# mini_ups.net
KiCad netlist of a schematic drawn in Altium Designer
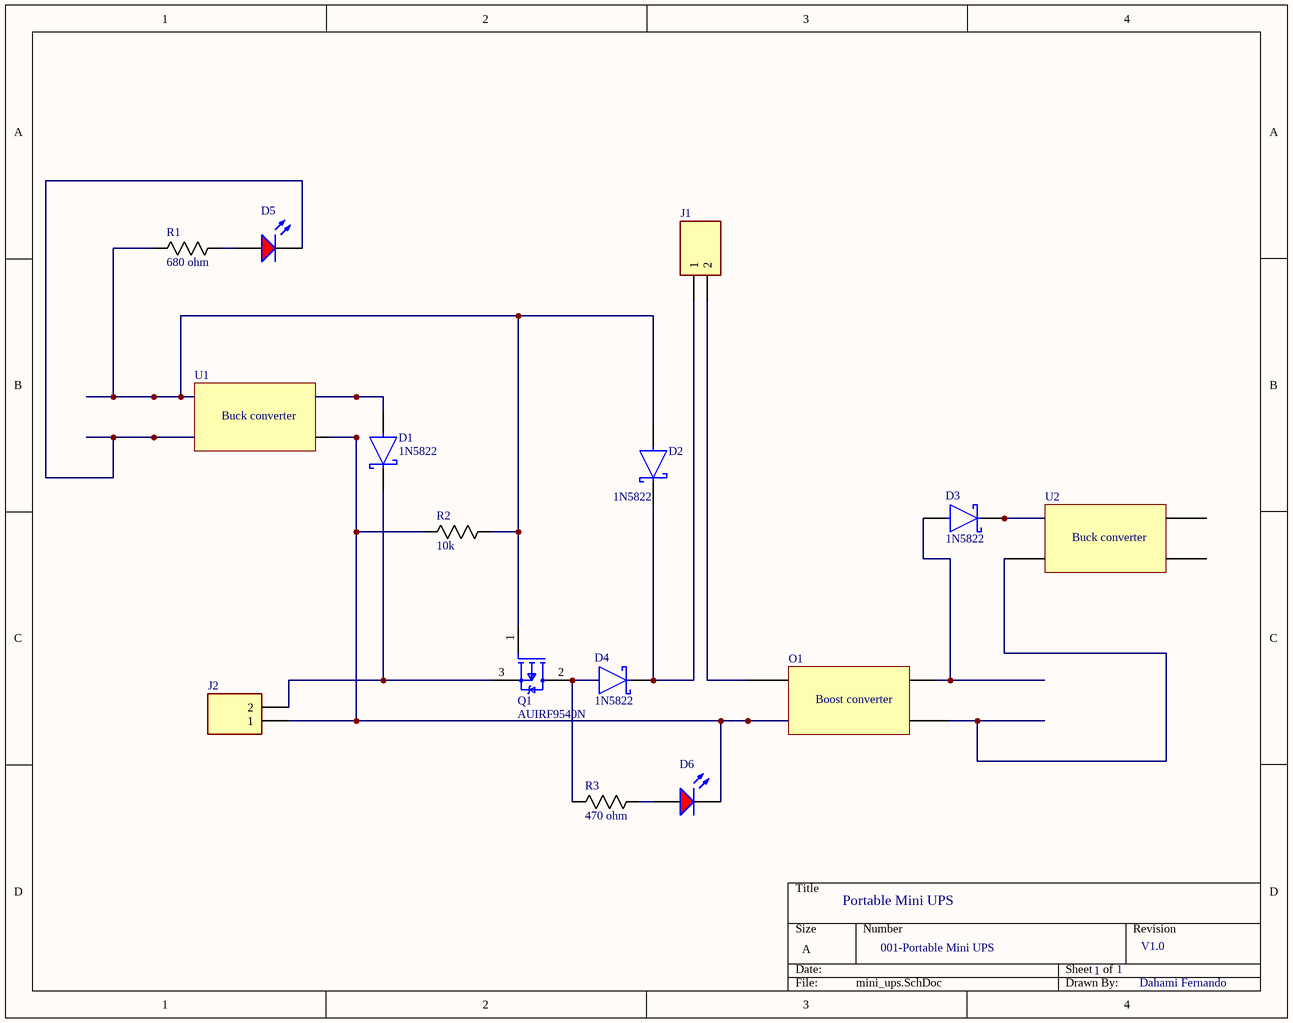
[diagram p0: mini_ups.SchDoc]

(export (version "E")
  (design (tool "Eeschema 10.0.6"))
  (components
    (comp (ref "D1")
      (value "1N5822")
      (footprint "FP-DO-201AD-MFG")
      (description "DIODE SCHOTTKY 40V 3A DO201AD")
      (fields
        (field (name "OCTOPART") "https://octopart.com/1n5822-stmicroelectronics-323225")
        (field (name "MANUFACTURER") "STMicroelectronics")
      )
      (libsource (lib "Altium Content Vault") (part "1d6ec82d83fb6aee721767c19dac4b9"))
    )
    (comp (ref "D2")
      (value "1N5822")
      (footprint "FP-DO-201AD-MFG")
      (description "DIODE SCHOTTKY 40V 3A DO201AD")
      (fields
        (field (name "OCTOPART") "https://octopart.com/1n5822-stmicroelectronics-323225")
        (field (name "MANUFACTURER") "STMicroelectronics")
      )
      (libsource (lib "Altium Content Vault") (part "1d6ec82d83fb6aee721767c19dac4b9"))
    )
    (comp (ref "D3")
      (value "1N5822")
      (footprint "FP-DO-201AD-MFG")
      (description "DIODE SCHOTTKY 40V 3A DO201AD")
      (fields
        (field (name "OCTOPART") "https://octopart.com/1n5822-stmicroelectronics-323225")
        (field (name "MANUFACTURER") "STMicroelectronics")
      )
      (libsource (lib "Altium Content Vault") (part "1d6ec82d83fb6aee721767c19dac4b9"))
    )
    (comp (ref "D4")
      (value "1N5822")
      (footprint "FP-DO-201AD-MFG")
      (description "DIODE SCHOTTKY 40V 3A DO201AD")
      (fields
        (field (name "OCTOPART") "https://octopart.com/1n5822-stmicroelectronics-323225")
        (field (name "MANUFACTURER") "STMicroelectronics")
      )
      (libsource (lib "Altium Content Vault") (part "1d6ec82d83fb6aee721767c19dac4b9"))
    )
    (comp (ref "D5")
      (value "151033RS03000")
      (footprint "WL-TMRW_D3.9H10.5")
      (libsource (lib "Altium Content Vault") (part "LED_Red_2A-1K"))
    )
    (comp (ref "D6")
      (value "151033RS03000")
      (footprint "WL-TMRW_D3.9H10.5")
      (libsource (lib "Altium Content Vault") (part "LED_Red_2A-1K"))
    )
    (comp (ref "J1")
      (value "TB010-508-02BE")
      (footprint "CUI_TB010-508-02BE")
      (description "2~24 Poles, Screw Type, Horizontal, 5.08 Pitch, 26~12 (AWG), Terminal Block Connector")
      (fields (field (name "MF") "CUI Devices"))
      (libsource (lib "TB010-508-02BE") (part "TB010-508-02BE"))
    )
    (comp (ref "J2")
      (value "TB010-508-02BE")
      (footprint "CUI_TB010-508-02BE")
      (description "2~24 Poles, Screw Type, Horizontal, 5.08 Pitch, 26~12 (AWG), Terminal Block Connector")
      (fields (field (name "MF") "CUI Devices"))
      (libsource (lib "") (part "TB010-508-02BE_1"))
    )
    (comp (ref "O1")
      (value "Boost converter")
      (footprint "Boost")
      (description "Boost converter module")
      (libsource (lib "Eclipse") (part "Boost"))
    )
    (comp (ref "Q1")
      (value "AUIRF9540N")
      (footprint "FP-TO-220AB-MFG")
      (description "AUIRF9540N Automotive Q101 -100V Single P-Channel HEXFET Power MOSFET in a TO-220AB Package")
      (libsource (lib "Altium Content Vault") (part "0a5270dd5e0f7d999c9a43bdc78dc18"))
    )
    (comp (ref "R1")
      (value "680 ohm")
      (footprint "STA_CF14_STP")
      (description "No Description Available")
      (libsource (lib "CF14JT10K0") (part "CF14JT10K0"))
    )
    (comp (ref "R2")
      (value "10k")
      (footprint "STA_CF14_STP")
      (description "RES 10K OHM 5% 1/4W AXIAL")
      (libsource (lib "CF14JT10K0") (part "CF14JT10K0"))
    )
    (comp (ref "R3")
      (value "470 ohm")
      (footprint "STA_CF14_STP")
      (description "No Description Available")
      (libsource (lib "CF14JT10K0") (part "CF14JT10K0"))
    )
    (comp (ref "U1")
      (value "Buck converter")
      (footprint "Buck")
      (description "Buck converter module")
      (libsource (lib "Eclipse") (part "Buck"))
    )
    (comp (ref "U2")
      (value "Buck converter")
      (footprint "Buck")
      (description "Buck converter module")
      (libsource (lib "Eclipse") (part "Buck"))
    )
  )
  (nets
    (net (code "1") (name "Net-(D1-A)") (class "Default")
      (node (ref "D1") (pin "2") (pinfunction "A_2") (pintype "passive"))
      (node (ref "U1") (pin "4") (pinfunction "4_4") (pintype "passive"))
    )
    (net (code "2") (name "Net-(D1-C)") (class "Default")
      (node (ref "D1") (pin "1") (pinfunction "C_1") (pintype "passive"))
      (node (ref "J2") (pin "2") (pinfunction "2_2") (pintype "passive"))
      (node (ref "Q1") (pin "3") (pinfunction "S_3") (pintype "passive"))
    )
    (net (code "3") (name "Net-(D2-A)") (class "Default")
      (node (ref "D2") (pin "2") (pinfunction "A_2") (pintype "passive"))
      (node (ref "Q1") (pin "1") (pinfunction "G_1") (pintype "passive"))
      (node (ref "R1") (pin "1") (pinfunction "1_1") (pintype "passive"))
      (node (ref "R2") (pin "2") (pinfunction "2_2") (pintype "passive"))
      (node (ref "U1") (pin "1") (pinfunction "1_1") (pintype "passive"))
    )
    (net (code "4") (name "Net-(D2-C)") (class "Default")
      (node (ref "D2") (pin "1") (pinfunction "C_1") (pintype "passive"))
      (node (ref "D4") (pin "1") (pinfunction "C_1") (pintype "passive"))
      (node (ref "J1") (pin "1") (pinfunction "1_1") (pintype "passive"))
    )
    (net (code "5") (name "Net-(D3-A)") (class "Default")
      (node (ref "D3") (pin "2") (pinfunction "A_2") (pintype "passive"))
      (node (ref "O1") (pin "4") (pinfunction "4_4") (pintype "passive"))
    )
    (net (code "6") (name "Net-(D3-C)") (class "Default")
      (node (ref "D3") (pin "1") (pinfunction "C_1") (pintype "passive"))
      (node (ref "U2") (pin "1") (pinfunction "1_1") (pintype "passive"))
    )
    (net (code "7") (name "Net-(D4-A)") (class "Default")
      (node (ref "D4") (pin "2") (pinfunction "A_2") (pintype "passive"))
      (node (ref "Q1") (pin "2") (pinfunction "D_2") (pintype "passive"))
      (node (ref "R3") (pin "1") (pinfunction "1_1") (pintype "passive"))
    )
    (net (code "8") (name "Net-(D5-A)") (class "Default")
      (node (ref "D5") (pin "2") (pinfunction "A_2") (pintype "passive"))
      (node (ref "R1") (pin "2") (pinfunction "2_2") (pintype "passive"))
    )
    (net (code "9") (name "Net-(D5-K)") (class "Default")
      (node (ref "D5") (pin "1") (pinfunction "K_1") (pintype "passive"))
      (node (ref "U1") (pin "2") (pinfunction "2_2") (pintype "passive"))
    )
    (net (code "10") (name "Net-(D6-A)") (class "Default")
      (node (ref "D6") (pin "2") (pinfunction "A_2") (pintype "passive"))
      (node (ref "R3") (pin "2") (pinfunction "2_2") (pintype "passive"))
    )
    (net (code "11") (name "Net-(D6-K)") (class "Default")
      (node (ref "D6") (pin "1") (pinfunction "K_1") (pintype "passive"))
      (node (ref "J2") (pin "1") (pinfunction "1_1") (pintype "passive"))
      (node (ref "O1") (pin "2") (pinfunction "2_2") (pintype "passive"))
      (node (ref "R2") (pin "1") (pinfunction "1_1") (pintype "passive"))
      (node (ref "U1") (pin "3") (pinfunction "3_3") (pintype "passive"))
    )
    (net (code "12") (name "Net-(J1-Pad2)") (class "Default")
      (node (ref "J1") (pin "2") (pinfunction "2_2") (pintype "passive"))
      (node (ref "O1") (pin "1") (pinfunction "1_1") (pintype "passive"))
    )
    (net (code "13") (name "Net-(O1-Pad3)") (class "Default")
      (node (ref "O1") (pin "3") (pinfunction "3_3") (pintype "passive"))
      (node (ref "U2") (pin "2") (pinfunction "2_2") (pintype "passive"))
    )
    (net (code "14") (name "unconnected-(U2-Pad3)") (class "Default")
      (node (ref "U2") (pin "3") (pinfunction "3_3") (pintype "passive"))
    )
    (net (code "15") (name "unconnected-(U2-Pad4)") (class "Default")
      (node (ref "U2") (pin "4") (pinfunction "4_4") (pintype "passive"))
    )
  )
)
